# meteo_withoutProg.net
KiCad netlist of a schematic drawn in EAGLE
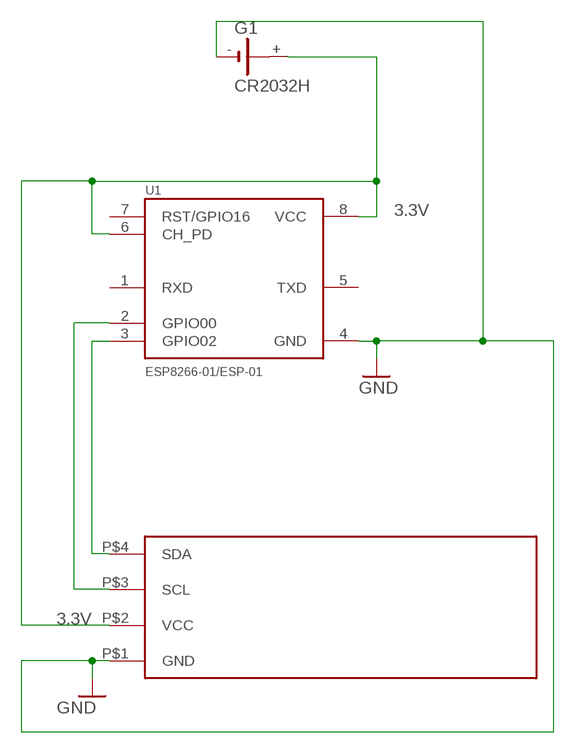
[diagram p0: schematic, sheet 1]

(export (version "E")
  (design (tool "Eeschema 10.0.6"))
  (components
    (comp (ref "G1")
      (value "CR2032H")
      (footprint "eagle-import:CR2032H")
      (libsource (lib "eagle-import") (part "CR2032H"))
    )
    (comp (ref "U$2")
      (value "OLED")
      (footprint "eagle-import:SIP")
      (libsource (lib "eagle-import") (part "OLED"))
    )
    (comp (ref "U1")
      (value "ESP8266-01/ESP-01")
      (footprint "eagle-import:XCVR_ESP8266-01_ESP-01")
      (fields (field (name "MF") "AI-Thinker"))
      (libsource (lib "eagle-import") (part "ESP8266-01/ESP-01"))
    )
  )
  (nets
    (net (code "1") (name "/3.3V") (class "Default")
      (node (ref "G1") (pin "+") (pinfunction "+_+") (pintype "passive"))
      (node (ref "U$2") (pin "P$2") (pinfunction "VCC_P$2") (pintype "bidirectional"))
      (node (ref "U1") (pin "6") (pinfunction "CH_PD_6") (pintype "input"))
      (node (ref "U1") (pin "8") (pinfunction "VCC_8") (pintype "power_in"))
    )
    (net (code "2") (name "GND") (class "Default")
      (node (ref "G1") (pin "-") (pinfunction "-_-") (pintype "passive"))
      (node (ref "U$2") (pin "P$1") (pinfunction "GND_P$1") (pintype "bidirectional"))
      (node (ref "U1") (pin "4") (pinfunction "GND_4") (pintype "power_in"))
    )
    (net (code "3") (name "Net-(U$2-SCL)") (class "Default")
      (node (ref "U$2") (pin "P$3") (pinfunction "SCL_P$3") (pintype "bidirectional"))
      (node (ref "U1") (pin "2") (pinfunction "GPIO00_2") (pintype "bidirectional"))
    )
    (net (code "4") (name "Net-(U$2-SDA)") (class "Default")
      (node (ref "U$2") (pin "P$4") (pinfunction "SDA_P$4") (pintype "bidirectional"))
      (node (ref "U1") (pin "3") (pinfunction "GPIO02_3") (pintype "bidirectional"))
    )
    (net (code "5") (name "unconnected-(G1-+-Pad+@1)") (class "Default")
      (node (ref "G1") (pin "+@1") (pinfunction "+_+@1") (pintype "passive"))
    )
    (net (code "6") (name "unconnected-(U1-RST{slash}GPIO16-Pad7)") (class "Default")
      (node (ref "U1") (pin "7") (pinfunction "RST/GPIO16_7") (pintype "input"))
    )
    (net (code "7") (name "unconnected-(U1-RXD-Pad1)") (class "Default")
      (node (ref "U1") (pin "1") (pinfunction "RXD_1") (pintype "input"))
    )
    (net (code "8") (name "unconnected-(U1-TXD-Pad5)") (class "Default")
      (node (ref "U1") (pin "5") (pinfunction "TXD_5") (pintype "output"))
    )
  )
)
